# MCU.net
KiCad netlist of a schematic drawn in Altium Designer
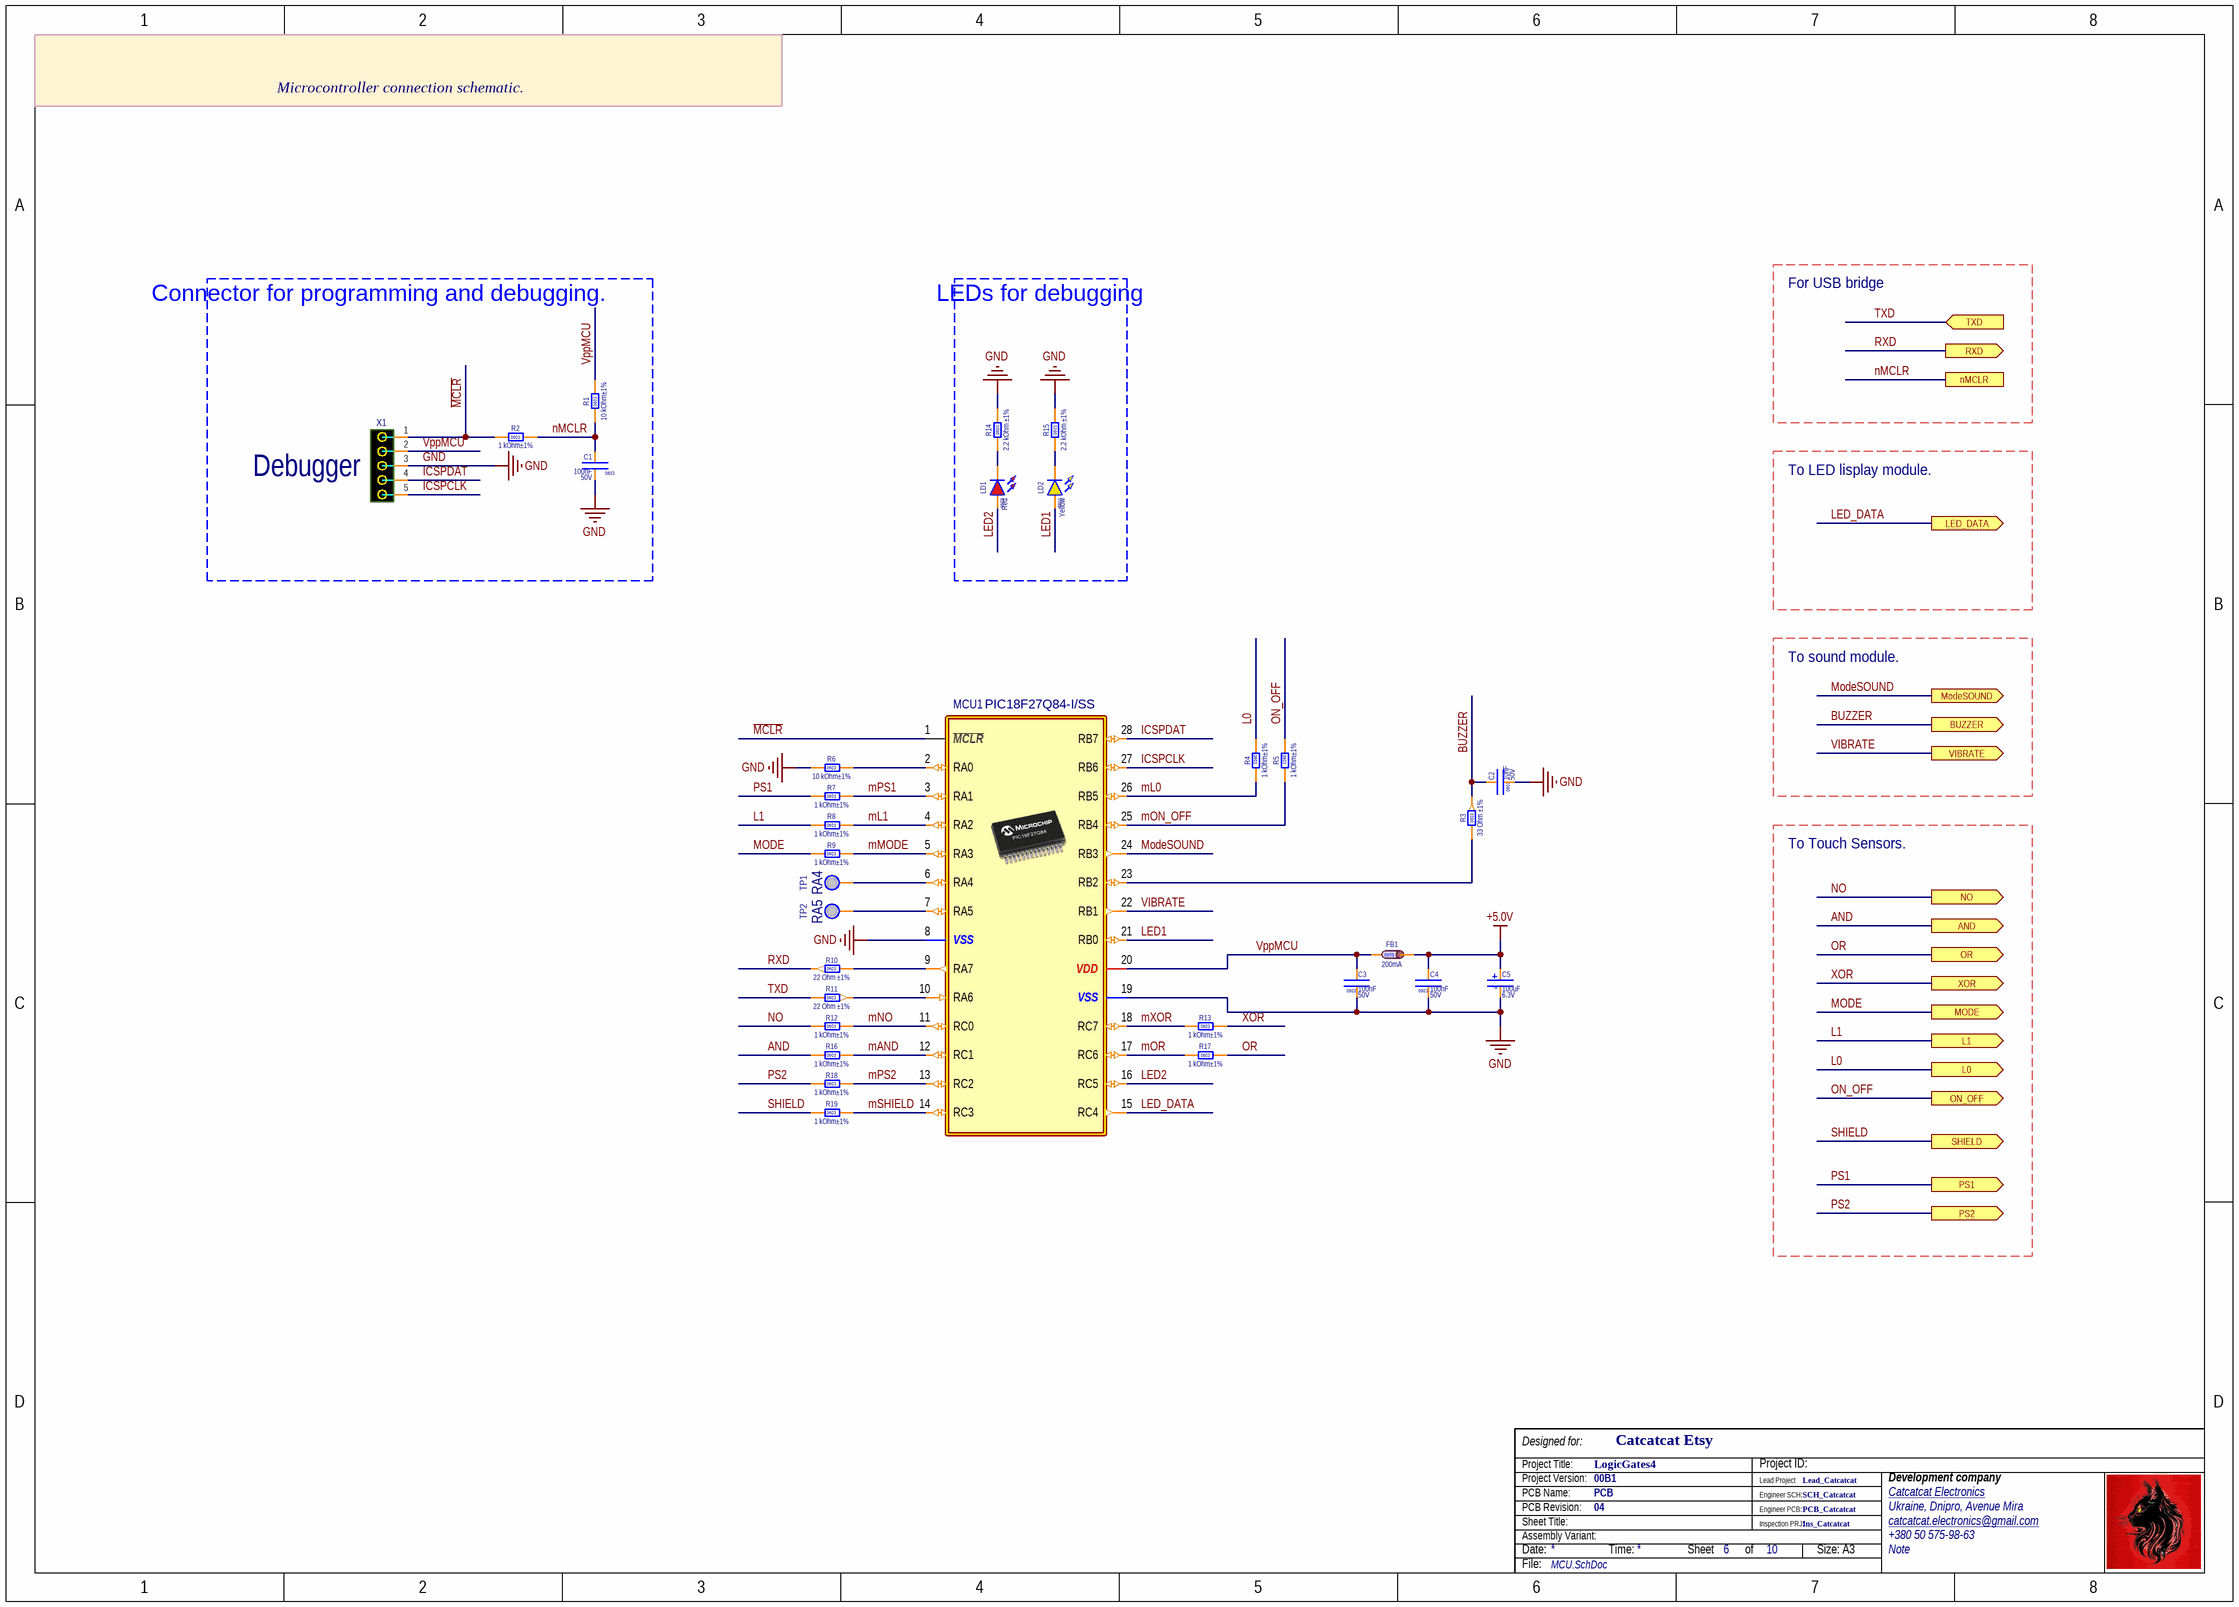
[diagram p0: MCU.SchDoc]

(export (version "E")
  (design (tool "Eeschema 10.0.6"))
  (components
    (comp (ref "C1")
      (value "100nF")
      (footprint "CC0603(1608)x0.8")
      (description "100 nF ±10% 50V X7R")
      (fields
        (field (name "TOLERANCE") "±10%")
        (field (name "VOLTAGE") "50V")
        (field (name "Comment") "100 nF ±10% 50V")
        (field (name "PUBLISHER") "Catcatcat Electronics")
      )
      (libsource (lib "IPC-7351chipCAPC") (part "0603 0.1 uF (B)"))
    )
    (comp (ref "C2")
      (value "10nF")
      (footprint "CC0603(1608)x0.8")
      (description "10 nF ±10% 50V X7R")
      (fields
        (field (name "TOLERANCE") "±10%")
        (field (name "VOLTAGE") "50V")
        (field (name "Comment") "10 nF ±10% 50V")
        (field (name "PUBLISHER") "Catcatcat Electronics")
      )
      (libsource (lib "IPC-7351chipCAPC") (part "0603 0.01 uF (B)"))
    )
    (comp (ref "C3")
      (value "100nF")
      (footprint "CC0603(1608)x0.8")
      (description "100 nF ±10% 50V X7R")
      (fields
        (field (name "TOLERANCE") "±10%")
        (field (name "VOLTAGE") "50V")
        (field (name "Comment") "100 nF ±10% 50V")
        (field (name "PUBLISHER") "Catcatcat Electronics")
      )
      (libsource (lib "IPC-7351chipCAPC") (part "0603 0.1 uF (B)"))
    )
    (comp (ref "C4")
      (value "100nF")
      (footprint "CC0603(1608)x0.8")
      (description "100 nF ±10% 50V X7R")
      (fields
        (field (name "TOLERANCE") "±10%")
        (field (name "VOLTAGE") "50V")
        (field (name "Comment") "100 nF ±10% 50V")
        (field (name "PUBLISHER") "Catcatcat Electronics")
      )
      (libsource (lib "IPC-7351chipCAPC") (part "0603 0.1 uF (B)"))
    )
    (comp (ref "C5")
      (value "100uF")
      (footprint "TANTAL_B")
      (description "Tantalum Capacitors 100uF 6.3V CASE-B_3528 RoHS")
      (fields
        (field (name "VOLTAGE") "6.3V")
        (field (name "Comment") "100UF 6.3V CASE-B_3528")
        (field (name "PUBLISHER") "Catcatcat Electronics")
      )
      (libsource (lib "CapacitorElectrolytic") (part "TANTAL-B 100uF 6.3V (B)"))
    )
    (comp (ref "FB1")
      (value "200mA")
      (footprint "FB0603(1608)")
      (description "0.20A 600 Ohm @100MHz 450 mOhm")
      (fields (field (name "Comment") "GZ1608D601TF") (field (name "PUBLISHER") "Catcatcat Electronics"))
      (libsource (lib "IPC-7351chipFEB") (part "0603 GZ1608D601TF (B)"))
    )
    (comp (ref "LD1")
      (value "Red")
      (footprint "LD0603 RED")
      (description "0603 Red 520~625NM 90~100MCD@20MA Top View RoHS")
      (fields
        (field (name "CASE/PACKAGE") "0603")
        (field (name "Comment") "KT-0603R")
        (field (name "PUBLISHER") "Catcatcat Electronics")
      )
      (libsource (lib "Led") (part "KT-0603R (B)"))
    )
    (comp (ref "LD2")
      (value "Yellow")
      (footprint "LD0603 YELLOW")
      (fields
        (field (name "CASE/PACKAGE") "0603")
        (field (name "Comment") "LED 0603 Yellow 120° 60mW")
        (field (name "PUBLISHER") "Catcatcat Electronics")
      )
      (libsource (lib "Led") (part "19-213/Y2C-CQ2R2L/3T(CY) (B)"))
    )
    (comp (ref "MCU1")
      (value "PIC18F27Q84-I/SS")
      (footprint "FP-C04-073-IPC_C")
      (description "SSOP-28, 128KB 1.8V~5.5V PIC 64MHz 25 SSOP-28-208mil Microcontroller Units (MCUs/MPUs/SOCs) ROHS")
      (fields (field (name "VOLTAGE") "1.8V~5.5V") (field (name "PUBLISHER") "Catcatcat Electronics"))
      (libsource (lib "MCU") (part "PIC18F27Q84-I/SS (E)"))
    )
    (comp (ref "R1")
      (value "10 kOhm±1%")
      (footprint "RC0603(1608) -1%")
      (description "10 k (103) ±1% 1/10W")
      (fields
        (field (name "TOLERANCE") "±1%")
        (field (name "VOLTAGE") "50V")
        (field (name "PUBLISHER") "Catcatcat Electronics")
      )
      (libsource (lib "IPC-7351chipRESC") (part "0603 10 kOhm ±1% (B)"))
    )
    (comp (ref "R2")
      (value "1 kOhm±1%")
      (footprint "RC0603(1608) -1%")
      (description "1 k (01B) ±1% 1/10W")
      (fields
        (field (name "TOLERANCE") "±1%")
        (field (name "VOLTAGE") "75V")
        (field (name "PUBLISHER") "Catcatcat Electronics")
      )
      (libsource (lib "IPC-7351chipRESC") (part "0603 1 kOhm ±1% (B)"))
    )
    (comp (ref "R3")
      (value "33 Ohm ±1%")
      (footprint "RC0603(1608) -1%")
      (description "33 R (330) ±1% 1/10W 50V")
      (fields
        (field (name "TOLERANCE") "±1%")
        (field (name "VOLTAGE") "50V")
        (field (name "PUBLISHER") "Catcatcat Electronics")
      )
      (libsource (lib "IPC-7351chipRESC") (part "0603 33 Ohm ±1% (B)"))
    )
    (comp (ref "R4")
      (value "1 kOhm±1%")
      (footprint "RC0603(1608) -1%")
      (description "1 k (01B) ±1% 1/10W")
      (fields
        (field (name "TOLERANCE") "±1%")
        (field (name "VOLTAGE") "75V")
        (field (name "PUBLISHER") "Catcatcat Electronics")
      )
      (libsource (lib "IPC-7351chipRESC") (part "0603 1 kOhm ±1% (B)"))
    )
    (comp (ref "R5")
      (value "1 kOhm±1%")
      (footprint "RC0603(1608) -1%")
      (description "1 k (01B) ±1% 1/10W")
      (fields
        (field (name "TOLERANCE") "±1%")
        (field (name "VOLTAGE") "75V")
        (field (name "PUBLISHER") "Catcatcat Electronics")
      )
      (libsource (lib "IPC-7351chipRESC") (part "0603 1 kOhm ±1% (B)"))
    )
    (comp (ref "R6")
      (value "10 kOhm±1%")
      (footprint "RC0603(1608) -1%")
      (description "10 k (103) ±1% 1/10W")
      (fields
        (field (name "TOLERANCE") "±1%")
        (field (name "VOLTAGE") "50V")
        (field (name "PUBLISHER") "Catcatcat Electronics")
      )
      (libsource (lib "IPC-7351chipRESC") (part "0603 10 kOhm ±1% (B)"))
    )
    (comp (ref "R7")
      (value "1 kOhm±1%")
      (footprint "RC0603(1608) -1%")
      (description "1 k (01B) ±1% 1/10W")
      (fields
        (field (name "TOLERANCE") "±1%")
        (field (name "VOLTAGE") "75V")
        (field (name "PUBLISHER") "Catcatcat Electronics")
      )
      (libsource (lib "IPC-7351chipRESC") (part "0603 1 kOhm ±1% (B)"))
    )
    (comp (ref "R8")
      (value "1 kOhm±1%")
      (footprint "RC0603(1608) -1%")
      (description "1 k (01B) ±1% 1/10W")
      (fields
        (field (name "TOLERANCE") "±1%")
        (field (name "VOLTAGE") "75V")
        (field (name "PUBLISHER") "Catcatcat Electronics")
      )
      (libsource (lib "IPC-7351chipRESC") (part "0603 1 kOhm ±1% (B)"))
    )
    (comp (ref "R9")
      (value "1 kOhm±1%")
      (footprint "RC0603(1608) -1%")
      (description "1 k (01B) ±1% 1/10W")
      (fields
        (field (name "TOLERANCE") "±1%")
        (field (name "VOLTAGE") "75V")
        (field (name "PUBLISHER") "Catcatcat Electronics")
      )
      (libsource (lib "IPC-7351chipRESC") (part "0603 1 kOhm ±1% (B)"))
    )
    (comp (ref "R10")
      (value "22 Ohm ±1%")
      (footprint "RC0603(1608) -1%")
      (description "22 R (220) ±1% 1/10W 50V")
      (fields
        (field (name "TOLERANCE") "±1%")
        (field (name "VOLTAGE") "50V")
        (field (name "PUBLISHER") "Catcatcat Electronics")
      )
      (libsource (lib "IPC-7351chipRESC") (part "0603 22 Ohm ±1% (B)"))
    )
    (comp (ref "R11")
      (value "22 Ohm ±1%")
      (footprint "RC0603(1608) -1%")
      (description "22 R (220) ±1% 1/10W 50V")
      (fields
        (field (name "TOLERANCE") "±1%")
        (field (name "VOLTAGE") "50V")
        (field (name "PUBLISHER") "Catcatcat Electronics")
      )
      (libsource (lib "IPC-7351chipRESC") (part "0603 22 Ohm ±1% (B)"))
    )
    (comp (ref "R12")
      (value "1 kOhm±1%")
      (footprint "RC0603(1608) -1%")
      (description "1 k (01B) ±1% 1/10W")
      (fields
        (field (name "TOLERANCE") "±1%")
        (field (name "VOLTAGE") "75V")
        (field (name "PUBLISHER") "Catcatcat Electronics")
      )
      (libsource (lib "IPC-7351chipRESC") (part "0603 1 kOhm ±1% (B)"))
    )
    (comp (ref "R13")
      (value "1 kOhm±1%")
      (footprint "RC0603(1608) -1%")
      (description "1 k (01B) ±1% 1/10W")
      (fields
        (field (name "TOLERANCE") "±1%")
        (field (name "VOLTAGE") "75V")
        (field (name "PUBLISHER") "Catcatcat Electronics")
      )
      (libsource (lib "IPC-7351chipRESC") (part "0603 1 kOhm ±1% (B)"))
    )
    (comp (ref "R14")
      (value "2.2 kOhm ±1%")
      (footprint "RC0603(1608) -1%")
      (description "2.2 k (222) ±1% 1/10W 50V")
      (fields
        (field (name "TOLERANCE") "±1%")
        (field (name "VOLTAGE") "50V")
        (field (name "PUBLISHER") "Catcatcat Electronics")
      )
      (libsource (lib "IPC-7351chipRESC") (part "0603 2.2 kOhm ±1% (B)"))
    )
    (comp (ref "R15")
      (value "2.2 kOhm ±1%")
      (footprint "RC0603(1608) -1%")
      (description "2.2 k (222) ±1% 1/10W 50V")
      (fields
        (field (name "TOLERANCE") "±1%")
        (field (name "VOLTAGE") "50V")
        (field (name "PUBLISHER") "Catcatcat Electronics")
      )
      (libsource (lib "IPC-7351chipRESC") (part "0603 2.2 kOhm ±1% (B)"))
    )
    (comp (ref "R16")
      (value "1 kOhm±1%")
      (footprint "RC0603(1608) -1%")
      (description "1 k (01B) ±1% 1/10W")
      (fields
        (field (name "TOLERANCE") "±1%")
        (field (name "VOLTAGE") "75V")
        (field (name "PUBLISHER") "Catcatcat Electronics")
      )
      (libsource (lib "IPC-7351chipRESC") (part "0603 1 kOhm ±1% (B)"))
    )
    (comp (ref "R17")
      (value "1 kOhm±1%")
      (footprint "RC0603(1608) -1%")
      (description "1 k (01B) ±1% 1/10W")
      (fields
        (field (name "TOLERANCE") "±1%")
        (field (name "VOLTAGE") "75V")
        (field (name "PUBLISHER") "Catcatcat Electronics")
      )
      (libsource (lib "IPC-7351chipRESC") (part "0603 1 kOhm ±1% (B)"))
    )
    (comp (ref "R18")
      (value "1 kOhm±1%")
      (footprint "RC0603(1608) -1%")
      (description "1 k (01B) ±1% 1/10W")
      (fields
        (field (name "TOLERANCE") "±1%")
        (field (name "VOLTAGE") "75V")
        (field (name "PUBLISHER") "Catcatcat Electronics")
      )
      (libsource (lib "IPC-7351chipRESC") (part "0603 1 kOhm ±1% (B)"))
    )
    (comp (ref "R19")
      (value "1 kOhm±1%")
      (footprint "RC0603(1608) -1%")
      (description "1 k (01B) ±1% 1/10W")
      (fields
        (field (name "TOLERANCE") "±1%")
        (field (name "VOLTAGE") "75V")
        (field (name "PUBLISHER") "Catcatcat Electronics")
      )
      (libsource (lib "IPC-7351chipRESC") (part "0603 1 kOhm ±1% (B)"))
    )
    (comp (ref "TP1")
      (value "RA4")
      (footprint "Test_Point_T_0.6mm")
      (description "Test Point TOP")
      (fields (field (name "PUBLISHER") "Catcatcat Electronics"))
      (libsource (lib "Assembly") (part "Test_Point smd_0.6"))
    )
    (comp (ref "TP2")
      (value "RA5")
      (footprint "Test_Point_T_0.6mm")
      (description "Test Point TOP")
      (fields (field (name "PUBLISHER") "Catcatcat Electronics"))
      (libsource (lib "Assembly") (part "Test_Point smd_0.6"))
    )
    (comp (ref "X1")
      (value "PL2N-05n")
      (footprint "PL2N-05")
      (description "2.0 mm")
      (fields (field (name "PUBLISHER") "Catcatcat Electronics"))
      (libsource (lib "ConnectorBoardToBoard") (part "PL2N-05n"))
    )
  )
  (nets
    (net (code "1") (name "+5.0V") (class "Default")
      (node (ref "C4") (pin "2") (pintype "passive"))
      (node (ref "C5") (pin "1") (pintype "passive"))
      (node (ref "FB1") (pin "1") (pintype "passive"))
    )
    (net (code "2") (name "/AND") (class "Default") (node (ref "R16") (pin "2") (pintype "passive")))
    (net (code "3") (name "/BUZZER") (class "Default")
      (node (ref "C2") (pin "2") (pintype "passive"))
      (node (ref "R3") (pin "2") (pintype "output"))
    )
    (net (code "4") (name "/ICSPCLK") (class "Default")
      (node (ref "MCU1") (pin "27") (pinfunction "RB6_27") (pintype "bidirectional"))
      (node (ref "X1") (pin "5") (pintype "passive"))
    )
    (net (code "5") (name "/ICSPDAT") (class "Default")
      (node (ref "MCU1") (pin "28") (pinfunction "RB7_28") (pintype "bidirectional"))
      (node (ref "X1") (pin "4") (pintype "passive"))
    )
    (net (code "6") (name "/L0") (class "Default") (node (ref "R4") (pin "1") (pintype "passive")))
    (net (code "7") (name "/L1") (class "Default") (node (ref "R8") (pin "1") (pintype "passive")))
    (net (code "8") (name "/LED1") (class "Default")
      (node (ref "LD2") (pin "2") (pintype "passive"))
      (node (ref "MCU1") (pin "21") (pinfunction "RB0_21") (pintype "bidirectional"))
    )
    (net (code "9") (name "/LED2") (class "Default")
      (node (ref "LD1") (pin "2") (pintype "passive"))
      (node (ref "MCU1") (pin "16") (pinfunction "RC5_16") (pintype "bidirectional"))
    )
    (net (code "10") (name "/LED_DATA") (class "Default")
      (node (ref "MCU1") (pin "15") (pinfunction "RC4_15") (pintype "output"))
    )
    (net (code "11") (name "/MCLR") (class "Default")
      (node (ref "MCU1") (pin "1") (pinfunction "~{MCLR}_1") (pintype "passive"))
      (node (ref "R2") (pin "2") (pintype "passive"))
      (node (ref "X1") (pin "1") (pintype "passive"))
    )
    (net (code "12") (name "/MODE") (class "Default") (node (ref "R9") (pin "2") (pintype "passive")))
    (net (code "13") (name "/ModeSOUND") (class "Default")
      (node (ref "MCU1") (pin "24") (pinfunction "RB3_24") (pintype "output"))
    )
    (net (code "14") (name "/NO") (class "Default") (node (ref "R12") (pin "2") (pintype "passive")))
    (net (code "15") (name "/ON_OFF") (class "Default") (node (ref "R5") (pin "1") (pintype "passive")))
    (net (code "16") (name "/OR") (class "Default") (node (ref "R17") (pin "2") (pintype "passive")))
    (net (code "17") (name "/PS1") (class "Default") (node (ref "R7") (pin "1") (pintype "passive")))
    (net (code "18") (name "/PS2") (class "Default") (node (ref "R18") (pin "2") (pintype "passive")))
    (net (code "19") (name "/RXD") (class "Default") (node (ref "R10") (pin "1") (pintype "output")))
    (net (code "20") (name "/SHIELD") (class "Default") (node (ref "R19") (pin "1") (pintype "passive")))
    (net (code "21") (name "/TXD") (class "Default") (node (ref "R11") (pin "1") (pintype "output")))
    (net (code "22") (name "/VIBRATE") (class "Default")
      (node (ref "MCU1") (pin "22") (pinfunction "RB1_22") (pintype "output"))
    )
    (net (code "23") (name "/VppMCU") (class "Default")
      (node (ref "C3") (pin "2") (pintype "passive"))
      (node (ref "FB1") (pin "2") (pintype "passive"))
      (node (ref "MCU1") (pin "20") (pinfunction "VDD_20") (pintype "passive"))
      (node (ref "R1") (pin "2") (pintype "passive"))
      (node (ref "X1") (pin "2") (pintype "passive"))
    )
    (net (code "24") (name "/XOR") (class "Default") (node (ref "R13") (pin "2") (pintype "passive")))
    (net (code "25") (name "/mAND") (class "Default")
      (node (ref "MCU1") (pin "12") (pinfunction "RC1_12") (pintype "bidirectional"))
      (node (ref "R16") (pin "1") (pintype "passive"))
    )
    (net (code "26") (name "/mL0") (class "Default")
      (node (ref "MCU1") (pin "26") (pinfunction "RB5_26") (pintype "bidirectional"))
      (node (ref "R4") (pin "2") (pintype "passive"))
    )
    (net (code "27") (name "/mL1") (class "Default")
      (node (ref "MCU1") (pin "4") (pinfunction "RA2_4") (pintype "bidirectional"))
      (node (ref "R8") (pin "2") (pintype "passive"))
    )
    (net (code "28") (name "/mMODE") (class "Default")
      (node (ref "MCU1") (pin "5") (pinfunction "RA3_5") (pintype "bidirectional"))
      (node (ref "R9") (pin "1") (pintype "passive"))
    )
    (net (code "29") (name "/mNO") (class "Default")
      (node (ref "MCU1") (pin "11") (pinfunction "RC0_11") (pintype "bidirectional"))
      (node (ref "R12") (pin "1") (pintype "passive"))
    )
    (net (code "30") (name "/mON_OFF") (class "Default")
      (node (ref "MCU1") (pin "25") (pinfunction "RB4_25") (pintype "bidirectional"))
      (node (ref "R5") (pin "2") (pintype "passive"))
    )
    (net (code "31") (name "/mOR") (class "Default")
      (node (ref "MCU1") (pin "17") (pinfunction "RC6_17") (pintype "bidirectional"))
      (node (ref "R17") (pin "1") (pintype "passive"))
    )
    (net (code "32") (name "/mPS1") (class "Default")
      (node (ref "MCU1") (pin "3") (pinfunction "RA1_3") (pintype "bidirectional"))
      (node (ref "R7") (pin "2") (pintype "passive"))
    )
    (net (code "33") (name "/mPS2") (class "Default")
      (node (ref "MCU1") (pin "13") (pinfunction "RC2_13") (pintype "bidirectional"))
      (node (ref "R18") (pin "1") (pintype "passive"))
    )
    (net (code "34") (name "/mSHIELD") (class "Default")
      (node (ref "MCU1") (pin "14") (pinfunction "RC3_14") (pintype "bidirectional"))
      (node (ref "R19") (pin "2") (pintype "passive"))
    )
    (net (code "35") (name "/mXOR") (class "Default")
      (node (ref "MCU1") (pin "18") (pinfunction "RC7_18") (pintype "bidirectional"))
      (node (ref "R13") (pin "1") (pintype "passive"))
    )
    (net (code "36") (name "/nMCLR") (class "Default")
      (node (ref "C1") (pin "2") (pintype "passive"))
      (node (ref "R1") (pin "1") (pintype "passive"))
      (node (ref "R2") (pin "1") (pintype "passive"))
    )
    (net (code "37") (name "GND") (class "Default")
      (node (ref "C1") (pin "1") (pintype "passive"))
      (node (ref "C2") (pin "1") (pintype "passive"))
      (node (ref "C3") (pin "1") (pintype "passive"))
      (node (ref "C4") (pin "1") (pintype "passive"))
      (node (ref "C5") (pin "2") (pintype "passive"))
      (node (ref "MCU1") (pin "19") (pinfunction "VSS_19") (pintype "power_in"))
      (node (ref "MCU1") (pin "8") (pinfunction "VSS_8") (pintype "power_in"))
      (node (ref "R14") (pin "1") (pintype "passive"))
      (node (ref "R15") (pin "1") (pintype "passive"))
      (node (ref "R6") (pin "1") (pintype "passive"))
      (node (ref "X1") (pin "3") (pintype "passive"))
    )
    (net (code "38") (name "Net-(LD1-Pad1)") (class "Default")
      (node (ref "LD1") (pin "1") (pintype "passive"))
      (node (ref "R14") (pin "2") (pintype "passive"))
    )
    (net (code "39") (name "Net-(LD2-Pad1)") (class "Default")
      (node (ref "LD2") (pin "1") (pintype "passive"))
      (node (ref "R15") (pin "2") (pintype "passive"))
    )
    (net (code "40") (name "Net-(MCU1-RA0)") (class "Default")
      (node (ref "MCU1") (pin "2") (pinfunction "RA0_2") (pintype "bidirectional"))
      (node (ref "R6") (pin "2") (pintype "passive"))
    )
    (net (code "41") (name "Net-(MCU1-RA4)") (class "Default")
      (node (ref "MCU1") (pin "6") (pinfunction "RA4_6") (pintype "bidirectional"))
      (node (ref "TP1") (pin "1") (pintype "passive"))
    )
    (net (code "42") (name "Net-(MCU1-RA5)") (class "Default")
      (node (ref "MCU1") (pin "7") (pinfunction "RA5_7") (pintype "bidirectional"))
      (node (ref "TP2") (pin "1") (pintype "passive"))
    )
    (net (code "43") (name "Net-(MCU1-RA6)") (class "Default")
      (node (ref "MCU1") (pin "10") (pinfunction "RA6_10") (pintype "input"))
      (node (ref "R11") (pin "2") (pintype "passive"))
    )
    (net (code "44") (name "Net-(MCU1-RA7)") (class "Default")
      (node (ref "MCU1") (pin "9") (pinfunction "RA7_9") (pintype "output"))
      (node (ref "R10") (pin "2") (pintype "passive"))
    )
    (net (code "45") (name "Net-(MCU1-RB2)") (class "Default")
      (node (ref "MCU1") (pin "23") (pinfunction "RB2_23") (pintype "bidirectional"))
      (node (ref "R3") (pin "1") (pintype "passive"))
    )
  )
)
